# main.net
KiCad netlist of a schematic drawn in Altium Designer
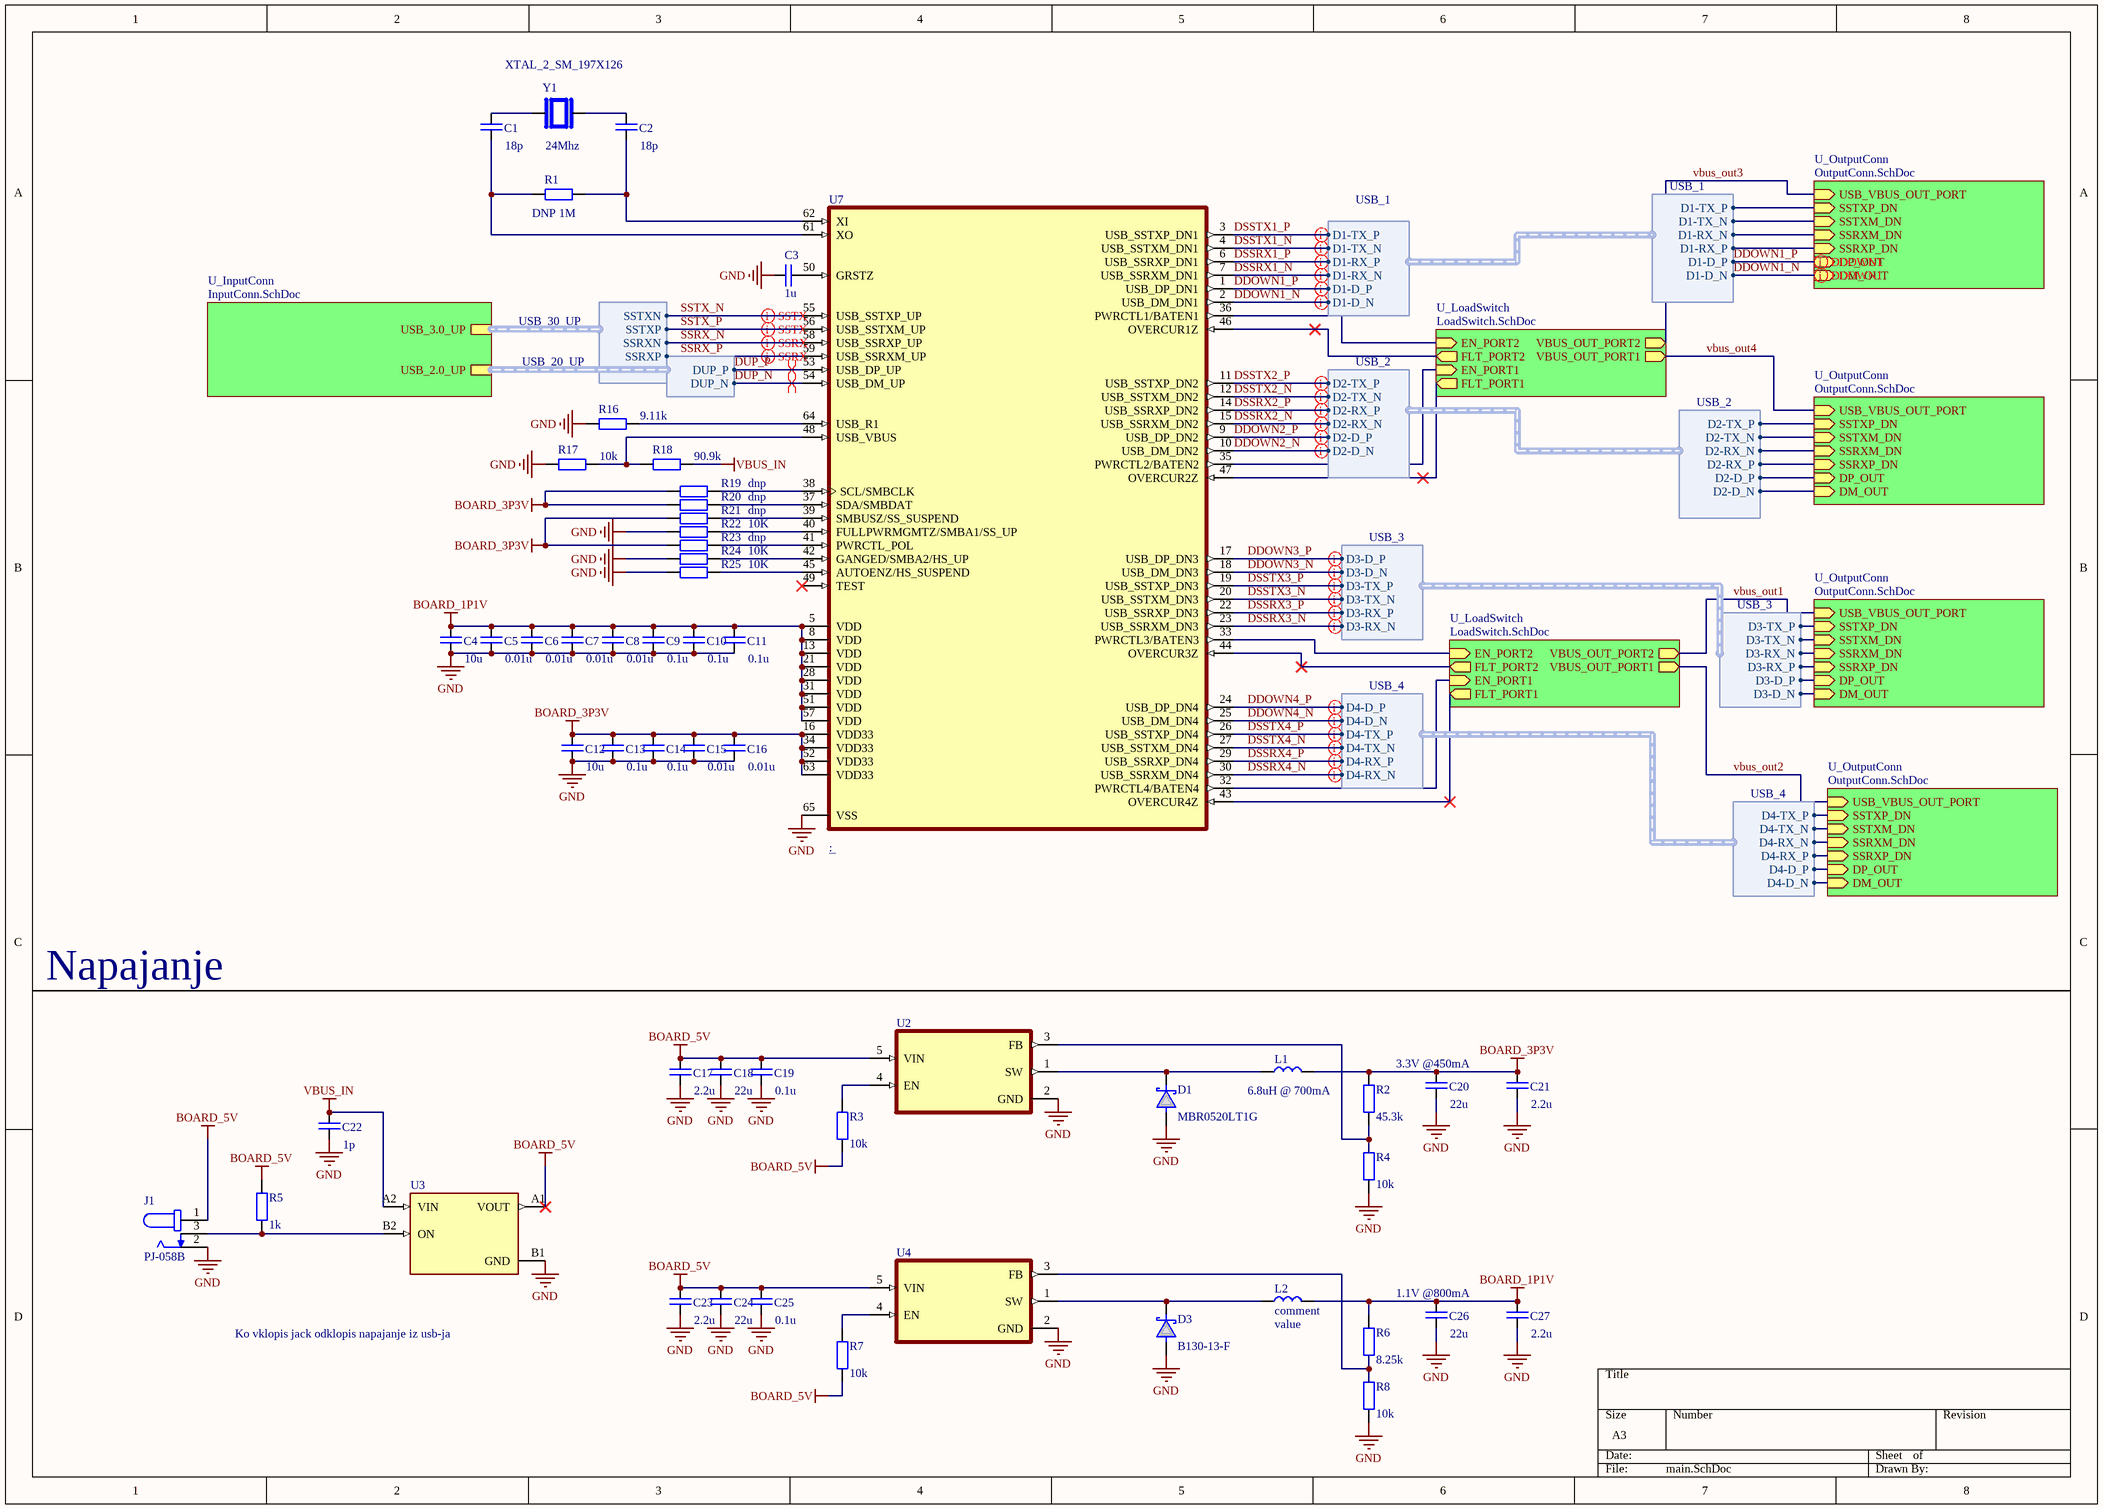
[diagram p0: main.SchDoc]

(export (version "E")
  (design (tool "Eeschema 10.0.6"))
  (components
    (comp (ref "C1")
      (value "18p")
      (footprint "CAP_0603_N")
      (fields (field (name "Comment") "comment"))
      (libsource (lib "USB-HUB1") (part "Capacitor non-polarized"))
    )
    (comp (ref "C2")
      (value "18p")
      (footprint "CAP_0603_N")
      (fields (field (name "Comment") "comment"))
      (libsource (lib "USB-HUB1") (part "Capacitor non-polarized"))
    )
    (comp (ref "C3")
      (value "1u")
      (footprint "CAP_0603_N")
      (fields (field (name "Comment") "comment"))
      (libsource (lib "USB-HUB1") (part "Capacitor non-polarized"))
    )
    (comp (ref "C4")
      (value "10u")
      (footprint "CAP_0603_N")
      (fields (field (name "Comment") "comment"))
      (libsource (lib "USB-HUB1") (part "Capacitor non-polarized"))
    )
    (comp (ref "C5")
      (value "0.01u")
      (footprint "CAP_0603_N")
      (fields (field (name "Comment") "comment"))
      (libsource (lib "USB-HUB1") (part "Capacitor non-polarized"))
    )
    (comp (ref "C6")
      (value "0.01u")
      (footprint "CAP_0603_N")
      (fields (field (name "Comment") "comment"))
      (libsource (lib "USB-HUB1") (part "Capacitor non-polarized"))
    )
    (comp (ref "C7")
      (value "0.01u")
      (footprint "CAP_0603_N")
      (fields (field (name "Comment") "comment"))
      (libsource (lib "USB-HUB1") (part "Capacitor non-polarized"))
    )
    (comp (ref "C8")
      (value "0.01u")
      (footprint "CAP_0603_N")
      (fields (field (name "Comment") "comment"))
      (libsource (lib "USB-HUB1") (part "Capacitor non-polarized"))
    )
    (comp (ref "C9")
      (value "0.1u")
      (footprint "CAP_0603_N")
      (fields (field (name "Comment") "comment"))
      (libsource (lib "USB-HUB1") (part "Capacitor non-polarized"))
    )
    (comp (ref "C10")
      (value "0.1u")
      (footprint "CAP_0603_N")
      (fields (field (name "Comment") "comment"))
      (libsource (lib "USB-HUB1") (part "Capacitor non-polarized"))
    )
    (comp (ref "C11")
      (value "0.1u")
      (footprint "CAP_0603_N")
      (fields (field (name "Comment") "comment"))
      (libsource (lib "USB-HUB1") (part "Capacitor non-polarized"))
    )
    (comp (ref "C12")
      (value "10u")
      (footprint "CAP_0603_N")
      (fields (field (name "Comment") "comment"))
      (libsource (lib "USB-HUB1") (part "Capacitor non-polarized"))
    )
    (comp (ref "C13")
      (value "0.1u")
      (footprint "CAP_0603_N")
      (fields (field (name "Comment") "comment"))
      (libsource (lib "USB-HUB1") (part "Capacitor non-polarized"))
    )
    (comp (ref "C14")
      (value "0.1u")
      (footprint "CAP_0603_N")
      (fields (field (name "Comment") "comment"))
      (libsource (lib "USB-HUB1") (part "Capacitor non-polarized"))
    )
    (comp (ref "C15")
      (value "0.01u")
      (footprint "CAP_0603_N")
      (fields (field (name "Comment") "comment"))
      (libsource (lib "USB-HUB1") (part "Capacitor non-polarized"))
    )
    (comp (ref "C16")
      (value "0.01u")
      (footprint "CAP_0603_N")
      (fields (field (name "Comment") "comment"))
      (libsource (lib "USB-HUB1") (part "Capacitor non-polarized"))
    )
    (comp (ref "C17")
      (value "2.2u")
      (footprint "CAP_0603_N")
      (fields (field (name "Comment") "comment"))
      (libsource (lib "USB-HUB1") (part "Capacitor non-polarized"))
    )
    (comp (ref "C18")
      (value "22u")
      (footprint "CAP_0603_N")
      (fields (field (name "Comment") "comment"))
      (libsource (lib "USB-HUB1") (part "Capacitor non-polarized"))
    )
    (comp (ref "C19")
      (value "0.1u")
      (footprint "CAP_0603_N")
      (fields (field (name "Comment") "comment"))
      (libsource (lib "USB-HUB1") (part "Capacitor non-polarized"))
    )
    (comp (ref "C20")
      (value "22u")
      (footprint "CAP_0603_N")
      (fields (field (name "Comment") "comment"))
      (libsource (lib "USB-HUB1") (part "Capacitor non-polarized"))
    )
    (comp (ref "C21")
      (value "2.2u")
      (footprint "CAP_0603_N")
      (fields (field (name "Comment") "comment"))
      (libsource (lib "USB-HUB1") (part "Capacitor non-polarized"))
    )
    (comp (ref "C22")
      (value "1p")
      (footprint "CAP_0603_N")
      (fields (field (name "Comment") "comment"))
      (libsource (lib "USB-HUB1") (part "Capacitor non-polarized"))
    )
    (comp (ref "C23")
      (value "2.2u")
      (footprint "CAP_0603_N")
      (fields (field (name "Comment") "comment"))
      (libsource (lib "USB-HUB1") (part "Capacitor non-polarized"))
    )
    (comp (ref "C24")
      (value "22u")
      (footprint "CAP_0603_N")
      (fields (field (name "Comment") "comment"))
      (libsource (lib "USB-HUB1") (part "Capacitor non-polarized"))
    )
    (comp (ref "C25")
      (value "0.1u")
      (footprint "CAP_0603_N")
      (fields (field (name "Comment") "comment"))
      (libsource (lib "USB-HUB1") (part "Capacitor non-polarized"))
    )
    (comp (ref "C26")
      (value "22u")
      (footprint "CAP_0603_N")
      (fields (field (name "Comment") "comment"))
      (libsource (lib "USB-HUB1") (part "Capacitor non-polarized"))
    )
    (comp (ref "C27")
      (value "2.2u")
      (footprint "CAP_0603_N")
      (fields (field (name "Comment") "comment"))
      (libsource (lib "USB-HUB1") (part "Capacitor non-polarized"))
    )
    (comp (ref "D1")
      (value "MBR0520LT1G")
      (footprint "SOD-123_N")
      (fields (field (name "Comment") "comment"))
      (libsource (lib "USB-HUB1") (part "Diode Schottky"))
    )
    (comp (ref "D3")
      (value "B130-13-F")
      (footprint "SOD-123_N")
      (fields (field (name "Comment") "comment"))
      (libsource (lib "USB-HUB1") (part "Diode Schottky"))
    )
    (comp (ref "J1")
      (value "PJ-058B")
      (footprint "CUI_PJ-058B")
      (description "2.5 mm Center Pin, 2.5 A, Right Angle, Through Hole, Locking Type, Dc Power Jack Connector")
      (libsource (lib "USB-HUB") (part "PJ-058B"))
    )
    (comp (ref "L1")
      (value "6.8uH @ 700mA")
      (footprint "SMD_1206_N")
      (fields (field (name "Comment") "comment"))
      (libsource (lib "USB-HUB1") (part "Inductor"))
    )
    (comp (ref "L2")
      (value "comment")
      (footprint "SMD_0603_N")
      (fields (field (name "ALTIUM_VALUE") "value"))
      (libsource (lib "USB-HUB1") (part "Inductor"))
    )
    (comp (ref "R1")
      (value "DNP")
      (footprint "SMD_0603_N")
      (fields (field (name "ALTIUM_VALUE") "1M"))
      (libsource (lib "USB-HUB1") (part "Resistor"))
    )
    (comp (ref "R2")
      (value "45.3k")
      (footprint "SMD_0603_N")
      (fields (field (name "Comment") "comment"))
      (libsource (lib "USB-HUB1") (part "Resistor"))
    )
    (comp (ref "R3")
      (value "10k")
      (footprint "SMD_0603_N")
      (fields (field (name "Comment") "comment"))
      (libsource (lib "USB-HUB1") (part "Resistor"))
    )
    (comp (ref "R4")
      (value "10k")
      (footprint "SMD_0603_N")
      (fields (field (name "Comment") "comment"))
      (libsource (lib "USB-HUB1") (part "Resistor"))
    )
    (comp (ref "R5")
      (value "1k")
      (footprint "SMD_0603_N")
      (fields (field (name "Comment") "comment"))
      (libsource (lib "USB-HUB1") (part "Resistor"))
    )
    (comp (ref "R6")
      (value "8.25k")
      (footprint "SMD_0603_N")
      (fields (field (name "Comment") "comment"))
      (libsource (lib "USB-HUB1") (part "Resistor"))
    )
    (comp (ref "R7")
      (value "10k")
      (footprint "SMD_0603_N")
      (fields (field (name "Comment") "comment"))
      (libsource (lib "USB-HUB1") (part "Resistor"))
    )
    (comp (ref "R8")
      (value "10k")
      (footprint "SMD_0603_N")
      (fields (field (name "Comment") "comment"))
      (libsource (lib "USB-HUB1") (part "Resistor"))
    )
    (comp (ref "R16")
      (value "9.11k")
      (footprint "SMD_0603_N")
      (fields (field (name "Comment") "DNP"))
      (libsource (lib "USB-HUB1") (part "Resistor"))
    )
    (comp (ref "R17")
      (value "10k")
      (footprint "SMD_0603_N")
      (fields (field (name "Comment") "DNP"))
      (libsource (lib "USB-HUB1") (part "Resistor"))
    )
    (comp (ref "R18")
      (value "90.9k")
      (footprint "SMD_0603_N")
      (fields (field (name "Comment") "DNP"))
      (libsource (lib "USB-HUB1") (part "Resistor"))
    )
    (comp (ref "R19")
      (value "dnp")
      (footprint "SMD_0603_N")
      (fields (field (name "Comment") "DNP"))
      (libsource (lib "USB-HUB1") (part "Resistor"))
    )
    (comp (ref "R20")
      (value "dnp")
      (footprint "SMD_0603_N")
      (fields (field (name "Comment") "DNP"))
      (libsource (lib "USB-HUB1") (part "Resistor"))
    )
    (comp (ref "R21")
      (value "dnp")
      (footprint "SMD_0603_N")
      (fields (field (name "Comment") "DNP"))
      (libsource (lib "USB-HUB1") (part "Resistor"))
    )
    (comp (ref "R22")
      (value "10K")
      (footprint "SMD_0603_N")
      (fields (field (name "Comment") "DNP"))
      (libsource (lib "USB-HUB1") (part "Resistor"))
    )
    (comp (ref "R23")
      (value "dnp")
      (footprint "SMD_0603_N")
      (fields (field (name "Comment") "DNP"))
      (libsource (lib "USB-HUB1") (part "Resistor"))
    )
    (comp (ref "R24")
      (value "10K")
      (footprint "SMD_0603_N")
      (fields (field (name "Comment") "DNP"))
      (libsource (lib "USB-HUB1") (part "Resistor"))
    )
    (comp (ref "R25")
      (value "10K")
      (footprint "SMD_0603_N")
      (fields (field (name "Comment") "DNP"))
      (libsource (lib "USB-HUB1") (part "Resistor"))
    )
    (comp (ref "U2")
      (value "~")
      (footprint "SOT95P280X145-5N")
      (fields (field (name "MP") "LMR10510XMFX/NOPB"))
      (libsource (lib "USB-HUB1") (part "LMR10510XMFX/NOPB"))
    )
    (comp (ref "U3")
      (value "~")
      (footprint "BGA4N50P2X2_88X88X50N")
      (description "5.5V, 2A, 61m? Active-Low Load Switch With Reverse Current Protection")
      (fields (field (name "MP") "TPS22910AYZVR"))
      (libsource (lib "USB-HUB1") (part "TPS22910AYZVR"))
    )
    (comp (ref "U4")
      (value "~")
      (footprint "SOT95P280X145-5N")
      (fields (field (name "MP") "LMR10510XMFX/NOPB"))
      (libsource (lib "USB-HUB1") (part "LMR10510XMFX/NOPB"))
    )
    (comp (ref "U7")
      (value "~")
      (footprint "QFN50P900X900X100-65N")
      (description "4-port 5-Gbps SuperSpeed USB 3.0 hub 64-VQFN 0 to 70")
      (fields (field (name "MF") "Texas Instruments") (field (name "MP") "TUSB8041RGCR"))
      (libsource (lib "USB-HUB1") (part "TUSB8041RGCR"))
    )
    (comp (ref "Y1")
      (value "XTAL_2_SM_197X126")
      (footprint "XTAL_CC7V-T1A-32.768KHZ-12.5PF-100PPM-TA-QC")
      (description "LOW FREQUENCY CRYSTAL")
      (fields
        (field (name "MF") "Micro Crystal AG")
        (field (name "ALTIUM_VALUE") "24Mhz")
        (field (name "MP") "CC7V-T1A-32.768KHZ-12.5PF-100PPM-TA-QC")
      )
      (libsource (lib "CC7V-T1A-32.768KHZ-12.5PF-100PPM-TA-QC") (part "CC7V-T1A-32.768KHZ-12.5PF-100PPM-TA-QC"))
    )
  )
  (nets
    (net (code "7") (name "/DDOWN1_N") (class "Default")
      (node (ref "U7") (pin "2") (pinfunction "USB_DM_DN1_2") (pintype "output"))
    )
    (net (code "8") (name "/DDOWN1_P") (class "Default")
      (node (ref "U7") (pin "1") (pinfunction "USB_DP_DN1_1") (pintype "output"))
    )
    (net (code "9") (name "/DDOWN2_N") (class "Default")
      (node (ref "U7") (pin "10") (pinfunction "USB_DM_DN2_10") (pintype "output"))
    )
    (net (code "10") (name "/DDOWN2_P") (class "Default")
      (node (ref "U7") (pin "9") (pinfunction "USB_DP_DN2_9") (pintype "output"))
    )
    (net (code "11") (name "/DDOWN3_N") (class "Default")
      (node (ref "U7") (pin "18") (pinfunction "USB_DM_DN3_18") (pintype "output"))
    )
    (net (code "12") (name "/DDOWN3_P") (class "Default")
      (node (ref "U7") (pin "17") (pinfunction "USB_DP_DN3_17") (pintype "output"))
    )
    (net (code "13") (name "/DDOWN4_N") (class "Default")
      (node (ref "U7") (pin "25") (pinfunction "USB_DM_DN4_25") (pintype "output"))
    )
    (net (code "14") (name "/DDOWN4_P") (class "Default")
      (node (ref "U7") (pin "24") (pinfunction "USB_DP_DN4_24") (pintype "output"))
    )
    (net (code "21") (name "/DSSRX1_N") (class "Default")
      (node (ref "U7") (pin "7") (pinfunction "USB_SSRXM_DN1_7") (pintype "output"))
    )
    (net (code "22") (name "/DSSRX1_P") (class "Default")
      (node (ref "U7") (pin "6") (pinfunction "USB_SSRXP_DN1_6") (pintype "output"))
    )
    (net (code "23") (name "/DSSRX2_N") (class "Default")
      (node (ref "U7") (pin "15") (pinfunction "USB_SSRXM_DN2_15") (pintype "output"))
    )
    (net (code "24") (name "/DSSRX2_P") (class "Default")
      (node (ref "U7") (pin "14") (pinfunction "USB_SSRXP_DN2_14") (pintype "output"))
    )
    (net (code "25") (name "/DSSRX3_N") (class "Default")
      (node (ref "U7") (pin "23") (pinfunction "USB_SSRXM_DN3_23") (pintype "output"))
    )
    (net (code "26") (name "/DSSRX3_P") (class "Default")
      (node (ref "U7") (pin "22") (pinfunction "USB_SSRXP_DN3_22") (pintype "output"))
    )
    (net (code "27") (name "/DSSRX4_N") (class "Default")
      (node (ref "U7") (pin "30") (pinfunction "USB_SSRXM_DN4_30") (pintype "output"))
    )
    (net (code "28") (name "/DSSRX4_P") (class "Default")
      (node (ref "U7") (pin "29") (pinfunction "USB_SSRXP_DN4_29") (pintype "output"))
    )
    (net (code "29") (name "/DSSTX1_N") (class "Default")
      (node (ref "U7") (pin "4") (pinfunction "USB_SSTXM_DN1_4") (pintype "output"))
    )
    (net (code "30") (name "/DSSTX1_P") (class "Default")
      (node (ref "U7") (pin "3") (pinfunction "USB_SSTXP_DN1_3") (pintype "output"))
    )
    (net (code "31") (name "/DSSTX2_N") (class "Default")
      (node (ref "U7") (pin "12") (pinfunction "USB_SSTXM_DN2_12") (pintype "output"))
    )
    (net (code "32") (name "/DSSTX2_P") (class "Default")
      (node (ref "U7") (pin "11") (pinfunction "USB_SSTXP_DN2_11") (pintype "output"))
    )
    (net (code "33") (name "/DSSTX3_N") (class "Default")
      (node (ref "U7") (pin "20") (pinfunction "USB_SSTXM_DN3_20") (pintype "output"))
    )
    (net (code "34") (name "/DSSTX3_P") (class "Default")
      (node (ref "U7") (pin "19") (pinfunction "USB_SSTXP_DN3_19") (pintype "output"))
    )
    (net (code "35") (name "/DSSTX4_N") (class "Default")
      (node (ref "U7") (pin "27") (pinfunction "USB_SSTXM_DN4_27") (pintype "output"))
    )
    (net (code "36") (name "/DSSTX4_P") (class "Default")
      (node (ref "U7") (pin "26") (pinfunction "USB_SSTXP_DN4_26") (pintype "output"))
    )
    (net (code "37") (name "/DUP_N") (class "Default")
      (node (ref "U7") (pin "54") (pinfunction "USB_DM_UP_54") (pintype "input"))
    )
    (net (code "38") (name "/DUP_P") (class "Default")
      (node (ref "U7") (pin "53") (pinfunction "USB_DP_UP_53") (pintype "input"))
    )
    (net (code "39") (name "/EN_PORT1") (class "Default")
      (node (ref "U7") (pin "35") (pinfunction "PWRCTL2/BATEN2_35") (pintype "output"))
    )
    (net (code "40") (name "/EN_PORT1_1") (class "Default")
      (node (ref "U7") (pin "32") (pinfunction "PWRCTL4/BATEN4_32") (pintype "output"))
    )
    (net (code "41") (name "/EN_PORT2") (class "Default")
      (node (ref "U7") (pin "36") (pinfunction "PWRCTL1/BATEN1_36") (pintype "output"))
    )
    (net (code "42") (name "/EN_PORT2_1") (class "Default")
      (node (ref "U7") (pin "33") (pinfunction "PWRCTL3/BATEN3_33") (pintype "output"))
    )
    (net (code "43") (name "/FLT_PORT1") (class "Default")
      (node (ref "U7") (pin "47") (pinfunction "OVERCUR2Z_47") (pintype "input"))
    )
    (net (code "44") (name "/FLT_PORT1_1") (class "Default")
      (node (ref "U7") (pin "43") (pinfunction "OVERCUR4Z_43") (pintype "input+no_connect"))
    )
    (net (code "45") (name "/FLT_PORT2") (class "Default")
      (node (ref "U7") (pin "46") (pinfunction "OVERCUR1Z_46") (pintype "input"))
    )
    (net (code "46") (name "/FLT_PORT2_1") (class "Default")
      (node (ref "U7") (pin "44") (pinfunction "OVERCUR3Z_44") (pintype "input+no_connect"))
    )
    (net (code "55") (name "/SSRX_N") (class "Default")
      (node (ref "U7") (pin "58") (pinfunction "USB_SSRXP_UP_58") (pintype "input"))
    )
    (net (code "56") (name "/SSRX_P") (class "Default")
      (node (ref "U7") (pin "59") (pinfunction "USB_SSRXM_UP_59") (pintype "input"))
    )
    (net (code "65") (name "/SSTX_N") (class "Default")
      (node (ref "U7") (pin "55") (pinfunction "USB_SSTXP_UP_55") (pintype "input"))
    )
    (net (code "66") (name "/SSTX_P") (class "Default")
      (node (ref "U7") (pin "56") (pinfunction "USB_SSTXM_UP_56") (pintype "input"))
    )
    (net (code "77") (name "BOARD_1P1V") (class "Default")
      (node (ref "C10") (pin "1") (pinfunction "1_1") (pintype "passive"))
      (node (ref "C11") (pin "1") (pinfunction "1_1") (pintype "passive"))
      (node (ref "C26") (pin "1") (pinfunction "1_1") (pintype "passive"))
      (node (ref "C27") (pin "1") (pinfunction "1_1") (pintype "passive"))
      (node (ref "C4") (pin "1") (pinfunction "1_1") (pintype "passive"))
      (node (ref "C5") (pin "1") (pinfunction "1_1") (pintype "passive"))
      (node (ref "C6") (pin "1") (pinfunction "1_1") (pintype "passive"))
      (node (ref "C7") (pin "1") (pinfunction "1_1") (pintype "passive"))
      (node (ref "C8") (pin "1") (pinfunction "1_1") (pintype "passive"))
      (node (ref "C9") (pin "1") (pinfunction "1_1") (pintype "passive"))
      (node (ref "L2") (pin "2") (pintype "passive"))
      (node (ref "R6") (pin "1") (pintype "passive"))
      (node (ref "U7") (pin "13") (pinfunction "VDD_13") (pintype "power_in"))
      (node (ref "U7") (pin "21") (pinfunction "VDD_21") (pintype "power_in"))
      (node (ref "U7") (pin "28") (pinfunction "VDD_28") (pintype "power_in"))
      (node (ref "U7") (pin "31") (pinfunction "VDD_31") (pintype "power_in"))
      (node (ref "U7") (pin "5") (pinfunction "VDD_5") (pintype "power_in"))
      (node (ref "U7") (pin "51") (pinfunction "VDD_51") (pintype "power_in"))
      (node (ref "U7") (pin "57") (pinfunction "VDD_57") (pintype "power_in"))
      (node (ref "U7") (pin "8") (pinfunction "VDD_8") (pintype "power_in"))
    )
    (net (code "78") (name "BOARD_3P3V") (class "Default")
      (node (ref "C12") (pin "1") (pinfunction "1_1") (pintype "passive"))
      (node (ref "C13") (pin "1") (pinfunction "1_1") (pintype "passive"))
      (node (ref "C14") (pin "1") (pinfunction "1_1") (pintype "passive"))
      (node (ref "C15") (pin "1") (pinfunction "1_1") (pintype "passive"))
      (node (ref "C16") (pin "1") (pinfunction "1_1") (pintype "passive"))
      (node (ref "C20") (pin "1") (pinfunction "1_1") (pintype "passive"))
      (node (ref "C21") (pin "1") (pinfunction "1_1") (pintype "passive"))
      (node (ref "L1") (pin "2") (pintype "passive"))
      (node (ref "R19") (pin "1") (pintype "passive"))
      (node (ref "R2") (pin "1") (pintype "passive"))
      (node (ref "R20") (pin "1") (pintype "passive"))
      (node (ref "R21") (pin "1") (pintype "passive"))
      (node (ref "R23") (pin "1") (pintype "passive"))
      (node (ref "U7") (pin "16") (pinfunction "VDD33_16") (pintype "power_in"))
      (node (ref "U7") (pin "34") (pinfunction "VDD33_34") (pintype "power_in"))
      (node (ref "U7") (pin "52") (pinfunction "VDD33_52") (pintype "power_in"))
      (node (ref "U7") (pin "63") (pinfunction "VDD33_63") (pintype "power_in"))
    )
    (net (code "79") (name "BOARD_5V") (class "Default")
      (node (ref "C17") (pin "1") (pinfunction "1_1") (pintype "passive"))
      (node (ref "C18") (pin "1") (pinfunction "1_1") (pintype "passive"))
      (node (ref "C19") (pin "1") (pinfunction "1_1") (pintype "passive"))
      (node (ref "C23") (pin "1") (pinfunction "1_1") (pintype "passive"))
      (node (ref "C24") (pin "1") (pinfunction "1_1") (pintype "passive"))
      (node (ref "C25") (pin "1") (pinfunction "1_1") (pintype "passive"))
      (node (ref "J1") (pin "1") (pinfunction "1_1") (pintype "passive"))
      (node (ref "R3") (pin "2") (pintype "passive"))
      (node (ref "R5") (pin "1") (pintype "passive"))
      (node (ref "R7") (pin "2") (pintype "passive"))
      (node (ref "U2") (pin "5") (pinfunction "VIN_5") (pintype "input"))
      (node (ref "U3") (pin "A1") (pinfunction "VOUT_A1") (pintype "output"))
      (node (ref "U4") (pin "5") (pinfunction "VIN_5") (pintype "input"))
    )
    (net (code "80") (name "GND") (class "Default")
      (node (ref "C10") (pin "2") (pinfunction "2_2") (pintype "passive"))
      (node (ref "C11") (pin "2") (pinfunction "2_2") (pintype "passive"))
      (node (ref "C12") (pin "2") (pinfunction "2_2") (pintype "passive"))
      (node (ref "C13") (pin "2") (pinfunction "2_2") (pintype "passive"))
      (node (ref "C14") (pin "2") (pinfunction "2_2") (pintype "passive"))
      (node (ref "C15") (pin "2") (pinfunction "2_2") (pintype "passive"))
      (node (ref "C16") (pin "2") (pinfunction "2_2") (pintype "passive"))
      (node (ref "C17") (pin "2") (pinfunction "2_2") (pintype "passive"))
      (node (ref "C18") (pin "2") (pinfunction "2_2") (pintype "passive"))
      (node (ref "C19") (pin "2") (pinfunction "2_2") (pintype "passive"))
      (node (ref "C20") (pin "2") (pinfunction "2_2") (pintype "passive"))
      (node (ref "C21") (pin "2") (pinfunction "2_2") (pintype "passive"))
      (node (ref "C22") (pin "2") (pinfunction "2_2") (pintype "passive"))
      (node (ref "C23") (pin "2") (pinfunction "2_2") (pintype "passive"))
      (node (ref "C24") (pin "2") (pinfunction "2_2") (pintype "passive"))
      (node (ref "C25") (pin "2") (pinfunction "2_2") (pintype "passive"))
      (node (ref "C26") (pin "2") (pinfunction "2_2") (pintype "passive"))
      (node (ref "C27") (pin "2") (pinfunction "2_2") (pintype "passive"))
      (node (ref "C3") (pin "1") (pinfunction "1_1") (pintype "passive"))
      (node (ref "C4") (pin "2") (pinfunction "2_2") (pintype "passive"))
      (node (ref "C5") (pin "2") (pinfunction "2_2") (pintype "passive"))
      (node (ref "C6") (pin "2") (pinfunction "2_2") (pintype "passive"))
      (node (ref "C7") (pin "2") (pinfunction "2_2") (pintype "passive"))
      (node (ref "C8") (pin "2") (pinfunction "2_2") (pintype "passive"))
      (node (ref "C9") (pin "2") (pinfunction "2_2") (pintype "passive"))
      (node (ref "D1") (pin "A") (pinfunction "A_A") (pintype "passive"))
      (node (ref "D3") (pin "A") (pinfunction "A_A") (pintype "passive"))
      (node (ref "J1") (pin "2") (pinfunction "2_2") (pintype "passive"))
      (node (ref "R16") (pin "1") (pintype "passive"))
      (node (ref "R17") (pin "1") (pintype "passive"))
      (node (ref "R22") (pin "1") (pintype "passive"))
      (node (ref "R24") (pin "1") (pintype "passive"))
      (node (ref "R25") (pin "1") (pintype "passive"))
      (node (ref "R4") (pin "2") (pintype "passive"))
      (node (ref "R8") (pin "2") (pintype "passive"))
      (node (ref "U2") (pin "2") (pinfunction "GND_2") (pintype "power_in"))
      (node (ref "U3") (pin "B1") (pinfunction "GND_B1") (pintype "power_in"))
      (node (ref "U4") (pin "2") (pinfunction "GND_2") (pintype "power_in"))
      (node (ref "U7") (pin "65") (pinfunction "VSS_65") (pintype "power_in"))
    )
    (net (code "81") (name "Net-(C1-Pad1)") (class "Default")
      (node (ref "C1") (pin "1") (pinfunction "1_1") (pintype "passive"))
      (node (ref "Y1") (pin "1") (pinfunction "1_1") (pintype "passive"))
    )
    (net (code "82") (name "Net-(C2-Pad1)") (class "Default")
      (node (ref "C2") (pin "1") (pinfunction "1_1") (pintype "passive"))
      (node (ref "Y1") (pin "2") (pinfunction "2_2") (pintype "passive"))
    )
    (net (code "83") (name "Net-(U2-EN)") (class "Default")
      (node (ref "R3") (pin "1") (pintype "passive"))
      (node (ref "U2") (pin "4") (pinfunction "EN_4") (pintype "input"))
    )
    (net (code "84") (name "Net-(U2-FB)") (class "Default")
      (node (ref "R2") (pin "2") (pintype "passive"))
      (node (ref "R4") (pin "1") (pintype "passive"))
      (node (ref "U2") (pin "3") (pinfunction "FB_3") (pintype "output"))
    )
    (net (code "85") (name "Net-(U2-SW)") (class "Default")
      (node (ref "D1") (pin "C") (pinfunction "C_C") (pintype "passive"))
      (node (ref "L1") (pin "1") (pintype "passive"))
      (node (ref "U2") (pin "1") (pinfunction "SW_1") (pintype "output"))
    )
    (net (code "86") (name "Net-(U3-ON)") (class "Default")
      (node (ref "J1") (pin "3") (pinfunction "3_3") (pintype "passive"))
      (node (ref "R5") (pin "2") (pintype "passive"))
      (node (ref "U3") (pin "B2") (pinfunction "ON_B2") (pintype "input"))
    )
    (net (code "87") (name "Net-(U4-EN)") (class "Default")
      (node (ref "R7") (pin "1") (pintype "passive"))
      (node (ref "U4") (pin "4") (pinfunction "EN_4") (pintype "input"))
    )
    (net (code "88") (name "Net-(U4-FB)") (class "Default")
      (node (ref "R6") (pin "2") (pintype "passive"))
      (node (ref "R8") (pin "1") (pintype "passive"))
      (node (ref "U4") (pin "3") (pinfunction "FB_3") (pintype "output"))
    )
    (net (code "89") (name "Net-(U4-SW)") (class "Default")
      (node (ref "D3") (pin "C") (pinfunction "C_C") (pintype "passive"))
      (node (ref "L2") (pin "1") (pintype "passive"))
      (node (ref "U4") (pin "1") (pinfunction "SW_1") (pintype "output"))
    )
    (net (code "90") (name "Net-(U7-AUTOENZ{slash}HS_SUSPEND)") (class "Default")
      (node (ref "R25") (pin "2") (pintype "passive"))
      (node (ref "U7") (pin "45") (pinfunction "AUTOENZ/HS_SUSPEND_45") (pintype "input"))
    )
    (net (code "91") (name "Net-(U7-FULLPWRMGMTZ{slash}SMBA1{slash}SS_UP)") (class "Default")
      (node (ref "R22") (pin "2") (pintype "passive"))
      (node (ref "U7") (pin "40") (pinfunction "FULLPWRMGMTZ/SMBA1/SS_UP_40") (pintype "input"))
    )
    (net (code "92") (name "Net-(U7-GANGED{slash}SMBA2{slash}HS_UP)") (class "Default")
      (node (ref "R24") (pin "2") (pintype "passive"))
      (node (ref "U7") (pin "42") (pinfunction "GANGED/SMBA2/HS_UP_42") (pintype "input"))
    )
    (net (code "93") (name "Net-(U7-GRSTZ)") (class "Default")
      (node (ref "C3") (pin "2") (pinfunction "2_2") (pintype "passive"))
      (node (ref "U7") (pin "50") (pinfunction "GRSTZ_50") (pintype "input"))
    )
    (net (code "94") (name "Net-(U7-PWRCTL_POL)") (class "Default")
      (node (ref "R23") (pin "2") (pintype "passive"))
      (node (ref "U7") (pin "41") (pinfunction "PWRCTL_POL_41") (pintype "input"))
    )
    (net (code "95") (name "Net-(U7-SCL{slash}SMBCLK)") (class "Default")
      (node (ref "R19") (pin "2") (pintype "passive"))
      (node (ref "U7") (pin "38") (pinfunction "SCL/SMBCLK_38") (pintype "input"))
    )
    (net (code "96") (name "Net-(U7-SDA{slash}SMBDAT)") (class "Default")
      (node (ref "R20") (pin "2") (pintype "passive"))
      (node (ref "U7") (pin "37") (pinfunction "SDA/SMBDAT_37") (pintype "input"))
    )
    (net (code "97") (name "Net-(U7-SMBUSZ{slash}SS_SUSPEND)") (class "Default")
      (node (ref "R21") (pin "2") (pintype "passive"))
      (node (ref "U7") (pin "39") (pinfunction "SMBUSZ/SS_SUSPEND_39") (pintype "input"))
    )
    (net (code "98") (name "Net-(U7-USB_R1)") (class "Default")
      (node (ref "R16") (pin "2") (pintype "passive"))
      (node (ref "U7") (pin "64") (pinfunction "USB_R1_64") (pintype "input"))
    )
    (net (code "99") (name "Net-(U7-USB_VBUS)") (class "Default")
      (node (ref "R17") (pin "2") (pintype "passive"))
      (node (ref "R18") (pin "1") (pintype "passive"))
      (node (ref "U7") (pin "48") (pinfunction "USB_VBUS_48") (pintype "input"))
    )
    (net (code "100") (name "Net-(U7-XI)") (class "Default")
      (node (ref "C2") (pin "2") (pinfunction "2_2") (pintype "passive"))
      (node (ref "R1") (pin "2") (pintype "passive"))
      (node (ref "U7") (pin "62") (pinfunction "XI_62") (pintype "input"))
    )
    (net (code "101") (name "Net-(U7-XO)") (class "Default")
      (node (ref "C1") (pin "2") (pinfunction "2_2") (pintype "passive"))
      (node (ref "R1") (pin "1") (pintype "passive"))
      (node (ref "U7") (pin "61") (pinfunction "XO_61") (pintype "input"))
    )
    (net (code "102") (name "VBUS_IN") (class "Default")
      (node (ref "C22") (pin "1") (pinfunction "1_1") (pintype "passive"))
      (node (ref "R18") (pin "2") (pintype "passive"))
      (node (ref "U3") (pin "A2") (pinfunction "VIN_A2") (pintype "input"))
    )
    (net (code "103") (name "unconnected-(U7-TEST-Pad49)") (class "Default")
      (node (ref "U7") (pin "49") (pinfunction "TEST_49") (pintype "input+no_connect"))
    )
  )
)
